# power_supply.net
KiCad netlist of a schematic drawn in Altium Designer
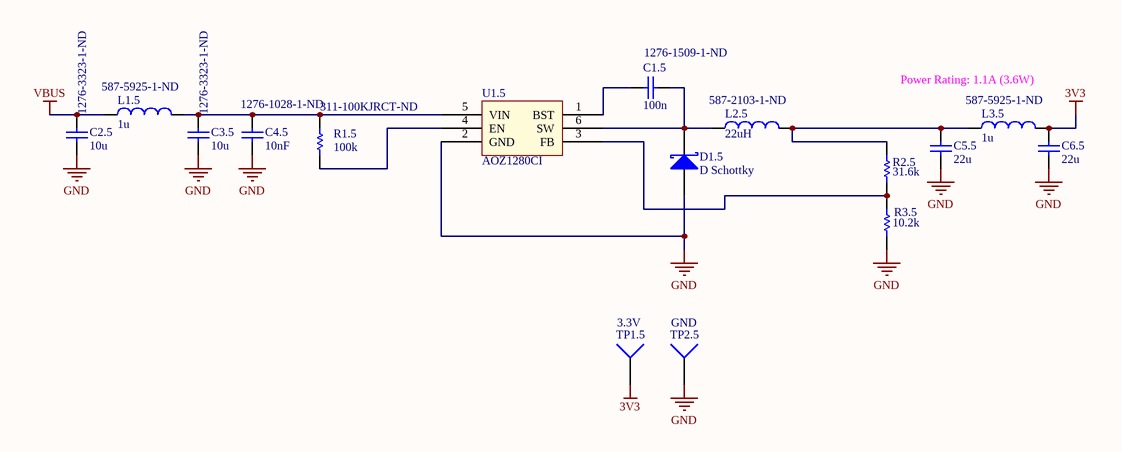
[diagram p0: power_supply.SchDoc]

(export (version "E")
  (design (tool "Eeschema 10.0.6"))
  (components
    (comp (ref "C1.5")
      (value "100n")
      (footprint "0402")
      (fields (field (name "SUPPLIER PART NUMBER 1") "1276-1509-1-ND"))
      (libsource (lib "Luminaire") (part "CAPACITOR NON_POL"))
    )
    (comp (ref "C2.5")
      (value "10u")
      (footprint "1210")
      (fields
        (field (name "SUPPLIER PART NUMBER 1") "1276-3323-1-ND")
        (field (name "TOLERANCE") "10%")
        (field (name "VOLTAGE") "35V")
      )
      (libsource (lib "Luminaire") (part "CAPACITOR NON_POL"))
    )
    (comp (ref "C3.5")
      (value "10u")
      (footprint "1210")
      (fields
        (field (name "SUPPLIER PART NUMBER 1") "1276-3323-1-ND")
        (field (name "TOLERANCE") "10%")
        (field (name "VOLTAGE") "35V")
      )
      (libsource (lib "Luminaire") (part "CAPACITOR NON_POL"))
    )
    (comp (ref "C4.5")
      (value "10nF")
      (footprint "0402")
      (fields (field (name "SUPPLIER PART NUMBER 1") "1276-1028-1-ND"))
      (libsource (lib "Luminaire") (part "CAPACITOR NON_POL"))
    )
    (comp (ref "C5.5")
      (value "22u")
      (footprint "0805")
      (fields
        (field (name "MANUFACTURER") "Murata Electronics North America")
        (field (name "MANUFACTURER PART NUMBER") "GRM21BR61A226ME44L")
        (field (name "TOLERANCE") "±20%")
      )
      (libsource (lib "Luminaire") (part "CAPACITOR NON_POL"))
    )
    (comp (ref "C6.5")
      (value "22u")
      (footprint "0805")
      (fields
        (field (name "MANUFACTURER") "Murata Electronics North America")
        (field (name "MANUFACTURER PART NUMBER") "GRM21BR61A226ME44L")
        (field (name "TOLERANCE") "±20%")
      )
      (libsource (lib "Luminaire") (part "CAPACITOR NON_POL"))
    )
    (comp (ref "D1.5")
      (value "D Schottky")
      (footprint "DO-214AC")
      (description "Schottky Diode")
      (fields
        (field (name "MANUFACTURER") "Diodes Incorporated")
        (field (name "MANUFACTURER PART NUMBER") "B240A-13-F")
      )
      (libsource (lib "Luminaire") (part "D Schottky"))
    )
    (comp (ref "L1.5")
      (value "1u")
      (footprint "0806")
      (description "Inductor")
      (fields
        (field (name "SUPPLIER PART NUMBER 1") "587-5925-1-ND")
        (field (name "MANUFACTURER") "Taiyo Yuden")
        (field (name "MANUFACTURER PART NUMBER") "MAKK2016T1R0M")
      )
      (libsource (lib "Luminaire") (part "Inductor"))
    )
    (comp (ref "L2.5")
      (value "22uH")
      (footprint "Murata 2900")
      (description "Inductor")
      (fields
        (field (name "MANUFACTURER") "Murata Power Solutions Inc")
        (field (name "MANUFACTURER PART NUMBER") "29L104C")
        (field (name "SUPPLIER PART NUMBER 1") "587-2103-1-ND")
        (field (name "PUBLISHER") "Altium Limited")
      )
      (libsource (lib "Miscellaneous Devices") (part "Inductor"))
    )
    (comp (ref "L3.5")
      (value "1u")
      (footprint "0806")
      (description "Inductor")
      (fields
        (field (name "SUPPLIER PART NUMBER 1") "587-5925-1-ND")
        (field (name "MANUFACTURER") "Taiyo Yuden")
        (field (name "MANUFACTURER PART NUMBER") "MAKK2016T1R0M")
      )
      (libsource (lib "Luminaire") (part "Inductor"))
    )
    (comp (ref "R1.5")
      (value "100k")
      (footprint "0402")
      (fields (field (name "SUPPLIER PART NUMBER 1") "311-100KJRCT-ND"))
      (libsource (lib "Panasonic Resistor") (part "ERJ2GE"))
    )
    (comp (ref "R2.5")
      (value "31.6k")
      (footprint "0402")
      (description "Resistor")
      (fields
        (field (name "MANUFACTURER") "Susumu")
        (field (name "MANUFACTURER PART NUMBER") "RR0510P-3322-D")
        (field (name "PUBLISHER") "Altium Limited")
      )
      (libsource (lib "Panasonic Resistor") (part "ERJ2GE"))
    )
    (comp (ref "R3.5")
      (value "10.2k")
      (footprint "0402")
      (description "Resistor")
      (fields
        (field (name "MANUFACTURER") "Stackpole Electronics Inc")
        (field (name "MANUFACTURER PART NUMBER") "RMCF0402FT14K3")
        (field (name "PUBLISHER") "Altium Limited")
      )
      (libsource (lib "Panasonic Resistor") (part "ERJ2GE"))
    )
    (comp (ref "TP1.5")
      (value "3.3V")
      (footprint "Test Point Target 1mm")
      (description "Socket")
      (fields (field (name "PUBLISHER") "Altium Limited"))
      (libsource (lib "Miscellaneous Connectors") (part "Socket"))
    )
    (comp (ref "TP2.5")
      (value "GND")
      (footprint "Test Point Target 1mm")
      (description "Socket")
      (fields (field (name "PUBLISHER") "Altium Limited"))
      (libsource (lib "Miscellaneous Connectors") (part "Socket"))
    )
    (comp (ref "U1.5")
      (value "~")
      (footprint "MK06A_N")
      (description "IC BUCK ADJ 1.2A 6TSOT")
      (fields
        (field (name "MANUFACTURER") "Alpha & Omega Semiconductor Inc.")
        (field (name "MANUFACTURER PART NUMBER") "AOZ1280CI")
      )
      (libsource (lib "Luminaire") (part "ADP2300"))
    )
  )
  (nets
    (net (code "1") (name "3V3") (class "Default")
      (node (ref "C6.5") (pin "2") (pinfunction "2_2") (pintype "passive"))
      (node (ref "L3.5") (pin "2") (pinfunction "2_2") (pintype "passive"))
      (node (ref "TP1.5") (pin "1") (pinfunction "1_1") (pintype "passive"))
    )
    (net (code "2") (name "GND") (class "Default")
      (node (ref "C2.5") (pin "1") (pinfunction "1_1") (pintype "passive"))
      (node (ref "C3.5") (pin "1") (pinfunction "1_1") (pintype "passive"))
      (node (ref "C4.5") (pin "1") (pinfunction "1_1") (pintype "passive"))
      (node (ref "C5.5") (pin "1") (pinfunction "1_1") (pintype "passive"))
      (node (ref "C6.5") (pin "1") (pinfunction "1_1") (pintype "passive"))
      (node (ref "D1.5") (pin "A") (pinfunction "A_A") (pintype "passive"))
      (node (ref "R3.5") (pin "1") (pinfunction "1_1") (pintype "passive"))
      (node (ref "TP2.5") (pin "1") (pinfunction "1_1") (pintype "passive"))
      (node (ref "U1.5") (pin "2") (pinfunction "GND_2") (pintype "passive"))
    )
    (net (code "3") (name "Net-(C5.5-Pad2)") (class "Default")
      (node (ref "C5.5") (pin "2") (pinfunction "2_2") (pintype "passive"))
      (node (ref "L2.5") (pin "2") (pinfunction "2_2") (pintype "passive"))
      (node (ref "L3.5") (pin "1") (pinfunction "1_1") (pintype "passive"))
      (node (ref "R2.5") (pin "2") (pinfunction "2_2") (pintype "passive"))
    )
    (net (code "4") (name "Net-(U1.5-BST)") (class "Default")
      (node (ref "C1.5") (pin "1") (pinfunction "1_1") (pintype "passive"))
      (node (ref "U1.5") (pin "1") (pinfunction "BST_1") (pintype "passive"))
    )
    (net (code "5") (name "Net-(U1.5-EN)") (class "Default")
      (node (ref "R1.5") (pin "1") (pinfunction "1_1") (pintype "passive"))
      (node (ref "U1.5") (pin "4") (pinfunction "EN_4") (pintype "passive"))
    )
    (net (code "6") (name "Net-(U1.5-FB)") (class "Default")
      (node (ref "R2.5") (pin "1") (pinfunction "1_1") (pintype "passive"))
      (node (ref "R3.5") (pin "2") (pinfunction "2_2") (pintype "passive"))
      (node (ref "U1.5") (pin "3") (pinfunction "FB_3") (pintype "passive"))
    )
    (net (code "7") (name "Net-(U1.5-SW)") (class "Default")
      (node (ref "C1.5") (pin "2") (pinfunction "2_2") (pintype "passive"))
      (node (ref "D1.5") (pin "K") (pinfunction "K_K") (pintype "passive"))
      (node (ref "L2.5") (pin "1") (pinfunction "1_1") (pintype "passive"))
      (node (ref "U1.5") (pin "6") (pinfunction "SW_6") (pintype "passive"))
    )
    (net (code "8") (name "Net-(U1.5-VIN)") (class "Default")
      (node (ref "C3.5") (pin "2") (pinfunction "2_2") (pintype "passive"))
      (node (ref "C4.5") (pin "2") (pinfunction "2_2") (pintype "passive"))
      (node (ref "L1.5") (pin "2") (pinfunction "2_2") (pintype "passive"))
      (node (ref "R1.5") (pin "2") (pinfunction "2_2") (pintype "passive"))
      (node (ref "U1.5") (pin "5") (pinfunction "VIN_5") (pintype "passive"))
    )
    (net (code "9") (name "VBUS") (class "Default")
      (node (ref "C2.5") (pin "2") (pinfunction "2_2") (pintype "passive"))
      (node (ref "L1.5") (pin "1") (pinfunction "1_1") (pintype "passive"))
    )
  )
)
